# pcb.net
KiCad netlist of a schematic drawn in EasyEDA Pro
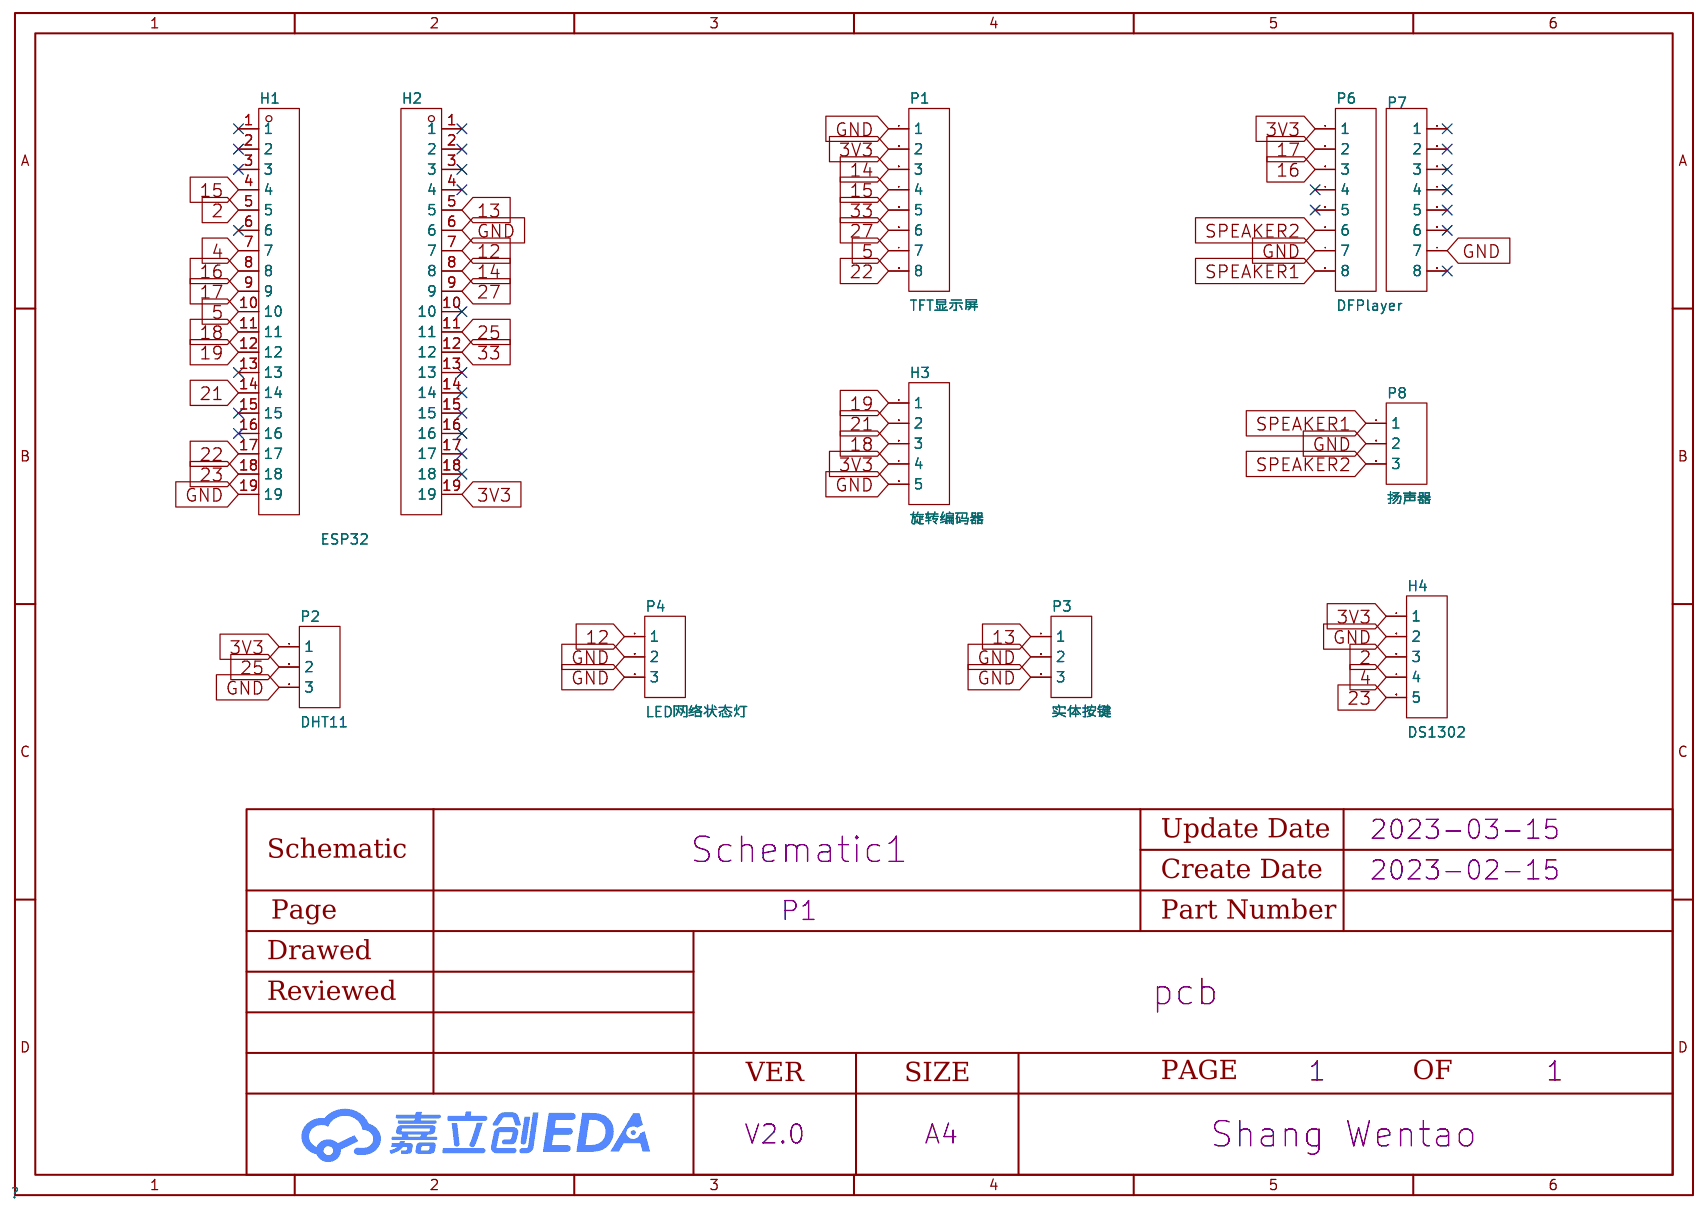
[diagram p0: schematic sheet]

(export (version "E")
  (design (tool "Eeschema 10.0.6"))
  (components
    (comp (ref "H1")
      (value "ESP32")
      (footprint "easyedapro:HDR-TH_19P-P2.54-V-F")
      (description "排数:单排;总孔位数:19;间距:2.54mm;行距:-;安装类型:直插;塑高:-;触头材质:-;触头镀层:-;")
      (fields (field (name "Manufacturer") "BOOMELE(博穆精密)"))
      (libsource (lib "easyedapro") (part "2.54-1*19P母"))
    )
    (comp (ref "H2")
      (value "ESP32")
      (footprint "easyedapro:HDR-TH_19P-P2.54-V-F")
      (description "排数:单排;总孔位数:19;间距:2.54mm;行距:-;安装类型:直插;塑高:-;触头材质:-;触头镀层:-;")
      (fields (field (name "Manufacturer") "BOOMELE(博穆精密)"))
      (libsource (lib "easyedapro") (part "2.54-1*19P母"))
    )
    (comp (ref "H3")
      (value "旋转编码器")
      (footprint "easyedapro:HDR-TH_5P-P2.54-V-F")
      (description "排数:单排;总孔位数:5;间距:2.54mm;插孔结构:1x5P;行距:-;安装类型:直插;塑高:-;触头材质:-;触头镀层:-;")
      (fields (field (name "Manufacturer") "BOOMELE(博穆精密)"))
      (libsource (lib "easyedapro") (part "Header-Female-2.54_1x5"))
    )
    (comp (ref "H4")
      (value "DS1302")
      (footprint "easyedapro:HDR-TH_5P-P2.54-V-F")
      (description "排数:单排;总孔位数:5;间距:2.54mm;插孔结构:1x5P;行距:-;安装类型:直插;塑高:-;触头材质:-;触头镀层:-;")
      (fields (field (name "Manufacturer") "BOOMELE(博穆精密)"))
      (libsource (lib "easyedapro") (part "Header-Female-2.54_1x5"))
    )
    (comp (ref "P1")
      (value "TFT显示屏")
      (footprint "easyedapro:HDR-TH_8P-P2.54-V-F-1")
      (description "排数:单排;总孔位数:8;间距:2.54mm;插孔结构:1x8P;行距:-;安装类型:直插;塑高:-;触头材质:-;触头镀层:-;")
      (fields (field (name "Manufacturer") "BOOMELE(博穆精密)"))
      (libsource (lib "easyedapro") (part "Header-Female-2.54_1x8"))
    )
    (comp (ref "P2")
      (value "DHT11")
      (footprint "easyedapro:HDR-TH_3P-P2.54-V-F")
      (description "排数:单排;总孔位数:3;间距:2.54mm;行距:-;安装类型:直插;塑高:-;触头材质:-;触头镀层:金;")
      (fields (field (name "Manufacturer") "BOOMELE(博穆精密)"))
      (libsource (lib "easyedapro") (part "Header-Female-2.54_1x3"))
    )
    (comp (ref "P3")
      (value "实体按键")
      (footprint "easyedapro:HDR-TH_3P-P2.54-V-F")
      (description "排数:单排;总孔位数:3;间距:2.54mm;行距:-;安装类型:直插;塑高:-;触头材质:-;触头镀层:金;")
      (fields (field (name "Manufacturer") "BOOMELE(博穆精密)"))
      (libsource (lib "easyedapro") (part "Header-Female-2.54_1x3"))
    )
    (comp (ref "P4")
      (value "LED网络状态灯")
      (footprint "easyedapro:HDR-TH_3P-P2.54-V-F")
      (description "排数:单排;总孔位数:3;间距:2.54mm;行距:-;安装类型:直插;塑高:-;触头材质:-;触头镀层:金;")
      (fields (field (name "Manufacturer") "BOOMELE(博穆精密)"))
      (libsource (lib "easyedapro") (part "Header-Female-2.54_1x3"))
    )
    (comp (ref "P6")
      (value "DFPlayer")
      (footprint "easyedapro:HDR-TH_8P-P2.54-V-F-1")
      (description "排数:单排;总孔位数:8;间距:2.54mm;插孔结构:1x8P;行距:-;安装类型:直插;塑高:-;触头材质:-;触头镀层:-;")
      (fields (field (name "Manufacturer") "BOOMELE(博穆精密)"))
      (libsource (lib "easyedapro") (part "Header-Female-2.54_1x8"))
    )
    (comp (ref "P7")
      (value "2.54-1*8P母环保")
      (footprint "easyedapro:HDR-TH_8P-P2.54-V-F-1")
      (description "排数:单排;总孔位数:8;间距:2.54mm;插孔结构:1x8P;行距:-;安装类型:直插;塑高:-;触头材质:-;触头镀层:-;")
      (fields (field (name "Manufacturer") "BOOMELE(博穆精密)"))
      (libsource (lib "easyedapro") (part "Header-Female-2.54_1x8"))
    )
    (comp (ref "P8")
      (value "扬声器")
      (footprint "easyedapro:HDR-TH_3P-P2.54-V-F")
      (description "排数:单排;总孔位数:3;间距:2.54mm;行距:-;安装类型:直插;塑高:-;触头材质:-;触头镀层:金;")
      (fields (field (name "Manufacturer") "BOOMELE(博穆精密)"))
      (libsource (lib "easyedapro") (part "Header-Female-2.54_1x3"))
    )
  )
  (nets
    (net (code "1") (name "2") (class "Default")
      (node (ref "H1") (pin "5") (pinfunction "5_5") (pintype "input"))
      (node (ref "H4") (pin "3") (pinfunction "3_3") (pintype "input"))
    )
    (net (code "2") (name "3V3") (class "Default")
      (node (ref "H2") (pin "19") (pinfunction "19_19") (pintype "input"))
      (node (ref "H3") (pin "4") (pinfunction "4_4") (pintype "input"))
      (node (ref "H4") (pin "1") (pinfunction "1_1") (pintype "input"))
      (node (ref "P1") (pin "2") (pinfunction "2_2") (pintype "input"))
      (node (ref "P2") (pin "1") (pinfunction "1_1") (pintype "input"))
      (node (ref "P6") (pin "1") (pinfunction "1_1") (pintype "input"))
    )
    (net (code "3") (name "4") (class "Default")
      (node (ref "H1") (pin "7") (pinfunction "7_7") (pintype "input"))
      (node (ref "H4") (pin "4") (pinfunction "4_4") (pintype "input"))
    )
    (net (code "4") (name "5") (class "Default")
      (node (ref "H1") (pin "10") (pinfunction "10_10") (pintype "input"))
      (node (ref "P1") (pin "7") (pinfunction "7_7") (pintype "input"))
    )
    (net (code "5") (name "12") (class "Default")
      (node (ref "H2") (pin "7") (pinfunction "7_7") (pintype "input"))
      (node (ref "P4") (pin "1") (pinfunction "1_1") (pintype "input"))
    )
    (net (code "6") (name "13") (class "Default")
      (node (ref "H2") (pin "5") (pinfunction "5_5") (pintype "input"))
      (node (ref "P3") (pin "1") (pinfunction "1_1") (pintype "input"))
    )
    (net (code "7") (name "14") (class "Default")
      (node (ref "H2") (pin "8") (pinfunction "8_8") (pintype "input"))
      (node (ref "P1") (pin "3") (pinfunction "3_3") (pintype "input"))
    )
    (net (code "8") (name "15") (class "Default")
      (node (ref "H1") (pin "4") (pinfunction "4_4") (pintype "input"))
      (node (ref "P1") (pin "4") (pinfunction "4_4") (pintype "input"))
    )
    (net (code "9") (name "16") (class "Default")
      (node (ref "H1") (pin "8") (pinfunction "8_8") (pintype "input"))
      (node (ref "P6") (pin "3") (pinfunction "3_3") (pintype "input"))
    )
    (net (code "10") (name "17") (class "Default")
      (node (ref "H1") (pin "9") (pinfunction "9_9") (pintype "input"))
      (node (ref "P6") (pin "2") (pinfunction "2_2") (pintype "input"))
    )
    (net (code "11") (name "18") (class "Default")
      (node (ref "H1") (pin "11") (pinfunction "11_11") (pintype "input"))
      (node (ref "H3") (pin "3") (pinfunction "3_3") (pintype "input"))
    )
    (net (code "12") (name "19") (class "Default")
      (node (ref "H1") (pin "12") (pinfunction "12_12") (pintype "input"))
      (node (ref "H3") (pin "1") (pinfunction "1_1") (pintype "input"))
    )
    (net (code "13") (name "21") (class "Default")
      (node (ref "H1") (pin "14") (pinfunction "14_14") (pintype "input"))
      (node (ref "H3") (pin "2") (pinfunction "2_2") (pintype "input"))
    )
    (net (code "14") (name "22") (class "Default")
      (node (ref "H1") (pin "17") (pinfunction "17_17") (pintype "input"))
      (node (ref "P1") (pin "8") (pinfunction "8_8") (pintype "input"))
    )
    (net (code "15") (name "23") (class "Default")
      (node (ref "H1") (pin "18") (pinfunction "18_18") (pintype "input"))
      (node (ref "H4") (pin "5") (pinfunction "5_5") (pintype "input"))
    )
    (net (code "16") (name "25") (class "Default")
      (node (ref "H2") (pin "11") (pinfunction "11_11") (pintype "input"))
      (node (ref "P2") (pin "2") (pinfunction "2_2") (pintype "input"))
    )
    (net (code "17") (name "27") (class "Default")
      (node (ref "H2") (pin "9") (pinfunction "9_9") (pintype "input"))
      (node (ref "P1") (pin "6") (pinfunction "6_6") (pintype "input"))
    )
    (net (code "18") (name "33") (class "Default")
      (node (ref "H2") (pin "12") (pinfunction "12_12") (pintype "input"))
      (node (ref "P1") (pin "5") (pinfunction "5_5") (pintype "input"))
    )
    (net (code "19") (name "GND") (class "Default")
      (node (ref "H1") (pin "19") (pinfunction "19_19") (pintype "input"))
      (node (ref "H2") (pin "6") (pinfunction "6_6") (pintype "input"))
      (node (ref "H3") (pin "5") (pinfunction "5_5") (pintype "input"))
      (node (ref "H4") (pin "2") (pinfunction "2_2") (pintype "input"))
      (node (ref "P1") (pin "1") (pinfunction "1_1") (pintype "input"))
      (node (ref "P2") (pin "3") (pinfunction "3_3") (pintype "input"))
      (node (ref "P3") (pin "2") (pinfunction "2_2") (pintype "input"))
      (node (ref "P3") (pin "3") (pinfunction "3_3") (pintype "input"))
      (node (ref "P4") (pin "2") (pinfunction "2_2") (pintype "input"))
      (node (ref "P4") (pin "3") (pinfunction "3_3") (pintype "input"))
      (node (ref "P6") (pin "7") (pinfunction "7_7") (pintype "input"))
      (node (ref "P7") (pin "7") (pinfunction "7_7") (pintype "input"))
      (node (ref "P8") (pin "2") (pinfunction "2_2") (pintype "input"))
    )
    (net (code "20") (name "SPEAKER1") (class "Default")
      (node (ref "P6") (pin "8") (pinfunction "8_8") (pintype "input"))
      (node (ref "P8") (pin "1") (pinfunction "1_1") (pintype "input"))
    )
    (net (code "21") (name "SPEAKER2") (class "Default")
      (node (ref "P6") (pin "6") (pinfunction "6_6") (pintype "input"))
      (node (ref "P8") (pin "3") (pinfunction "3_3") (pintype "input"))
    )
    (net (code "22") (name "unconnected-(H1-Pad1)") (class "Default")
      (node (ref "H1") (pin "1") (pinfunction "1_1") (pintype "input+no_connect"))
    )
    (net (code "23") (name "unconnected-(H1-Pad2)") (class "Default")
      (node (ref "H1") (pin "2") (pinfunction "2_2") (pintype "input+no_connect"))
    )
    (net (code "24") (name "unconnected-(H1-Pad3)") (class "Default")
      (node (ref "H1") (pin "3") (pinfunction "3_3") (pintype "input+no_connect"))
    )
    (net (code "25") (name "unconnected-(H1-Pad6)") (class "Default")
      (node (ref "H1") (pin "6") (pinfunction "6_6") (pintype "input+no_connect"))
    )
    (net (code "26") (name "unconnected-(H1-Pad13)") (class "Default")
      (node (ref "H1") (pin "13") (pinfunction "13_13") (pintype "input+no_connect"))
    )
    (net (code "27") (name "unconnected-(H1-Pad15)") (class "Default")
      (node (ref "H1") (pin "15") (pinfunction "15_15") (pintype "input+no_connect"))
    )
    (net (code "28") (name "unconnected-(H1-Pad16)") (class "Default")
      (node (ref "H1") (pin "16") (pinfunction "16_16") (pintype "input+no_connect"))
    )
    (net (code "29") (name "unconnected-(H2-Pad1)") (class "Default")
      (node (ref "H2") (pin "1") (pinfunction "1_1") (pintype "input+no_connect"))
    )
    (net (code "30") (name "unconnected-(H2-Pad2)") (class "Default")
      (node (ref "H2") (pin "2") (pinfunction "2_2") (pintype "input+no_connect"))
    )
    (net (code "31") (name "unconnected-(H2-Pad3)") (class "Default")
      (node (ref "H2") (pin "3") (pinfunction "3_3") (pintype "input+no_connect"))
    )
    (net (code "32") (name "unconnected-(H2-Pad4)") (class "Default")
      (node (ref "H2") (pin "4") (pinfunction "4_4") (pintype "input+no_connect"))
    )
    (net (code "33") (name "unconnected-(H2-Pad10)") (class "Default")
      (node (ref "H2") (pin "10") (pinfunction "10_10") (pintype "input+no_connect"))
    )
    (net (code "34") (name "unconnected-(H2-Pad13)") (class "Default")
      (node (ref "H2") (pin "13") (pinfunction "13_13") (pintype "input+no_connect"))
    )
    (net (code "35") (name "unconnected-(H2-Pad14)") (class "Default")
      (node (ref "H2") (pin "14") (pinfunction "14_14") (pintype "input+no_connect"))
    )
    (net (code "36") (name "unconnected-(H2-Pad15)") (class "Default")
      (node (ref "H2") (pin "15") (pinfunction "15_15") (pintype "input+no_connect"))
    )
    (net (code "37") (name "unconnected-(H2-Pad16)") (class "Default")
      (node (ref "H2") (pin "16") (pinfunction "16_16") (pintype "input+no_connect"))
    )
    (net (code "38") (name "unconnected-(H2-Pad17)") (class "Default")
      (node (ref "H2") (pin "17") (pinfunction "17_17") (pintype "input+no_connect"))
    )
    (net (code "39") (name "unconnected-(H2-Pad18)") (class "Default")
      (node (ref "H2") (pin "18") (pinfunction "18_18") (pintype "input+no_connect"))
    )
    (net (code "40") (name "unconnected-(P6-Pad4)") (class "Default")
      (node (ref "P6") (pin "4") (pinfunction "4_4") (pintype "input+no_connect"))
    )
    (net (code "41") (name "unconnected-(P6-Pad5)") (class "Default")
      (node (ref "P6") (pin "5") (pinfunction "5_5") (pintype "input+no_connect"))
    )
    (net (code "42") (name "unconnected-(P7-Pad1)") (class "Default")
      (node (ref "P7") (pin "1") (pinfunction "1_1") (pintype "input+no_connect"))
    )
    (net (code "43") (name "unconnected-(P7-Pad2)") (class "Default")
      (node (ref "P7") (pin "2") (pinfunction "2_2") (pintype "input+no_connect"))
    )
    (net (code "44") (name "unconnected-(P7-Pad3)") (class "Default")
      (node (ref "P7") (pin "3") (pinfunction "3_3") (pintype "input+no_connect"))
    )
    (net (code "45") (name "unconnected-(P7-Pad4)") (class "Default")
      (node (ref "P7") (pin "4") (pinfunction "4_4") (pintype "input+no_connect"))
    )
    (net (code "46") (name "unconnected-(P7-Pad5)") (class "Default")
      (node (ref "P7") (pin "5") (pinfunction "5_5") (pintype "input+no_connect"))
    )
    (net (code "47") (name "unconnected-(P7-Pad6)") (class "Default")
      (node (ref "P7") (pin "6") (pinfunction "6_6") (pintype "input+no_connect"))
    )
    (net (code "48") (name "unconnected-(P7-Pad8)") (class "Default")
      (node (ref "P7") (pin "8") (pinfunction "8_8") (pintype "input+no_connect"))
    )
  )
)
